# MGT.net
KiCad netlist of a schematic drawn in Altium Designer
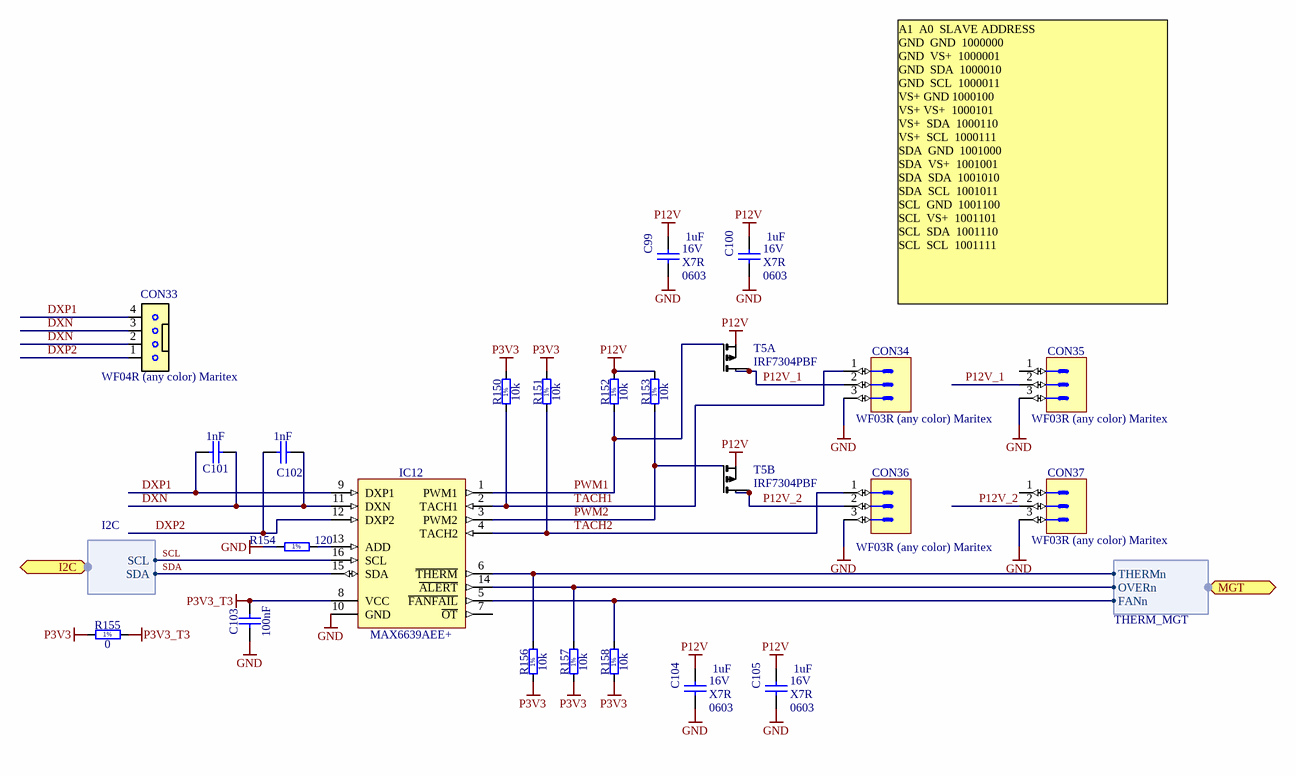
[diagram p0: MGT.SchDoc]

(export (version "E")
  (design (tool "Eeschema 10.0.6"))
  (components
    (comp (ref "C99")
      (value "1uF")
      (footprint "CAPC1608X87N")
      (description "Non-polarised capacitor")
      (fields
        (field (name "PART NUMBER") "CC0603_1UF_16V_10%_X7R")
        (field (name "VOLTAGE") "16V")
        (field (name "TC") "X7R")
        (field (name "TOLERANCE") "±10%")
        (field (name "CASE") "0603")
        (field (name "AUTHOR") "CERN DEM JLC")
      )
      (libsource (lib "Capacitors") (part "Capacitor - non polarized"))
    )
    (comp (ref "C100")
      (value "1uF")
      (footprint "CAPC1608X87N")
      (description "Non-polarised capacitor")
      (fields
        (field (name "PART NUMBER") "CC0603_1UF_16V_10%_X7R")
        (field (name "VOLTAGE") "16V")
        (field (name "TC") "X7R")
        (field (name "TOLERANCE") "±10%")
        (field (name "CASE") "0603")
        (field (name "AUTHOR") "CERN DEM JLC")
      )
      (libsource (lib "Capacitors") (part "Capacitor - non polarized"))
    )
    (comp (ref "C101")
      (value "1nF")
      (footprint "CAPC1608X87N")
      (description "Non-polarised capacitor")
      (fields
        (field (name "PART NUMBER") "CC0603_1NF_50V_10%_X7R")
        (field (name "VOLTAGE") "50V")
        (field (name "AUTHOR") "CERN DEM JLC")
      )
      (libsource (lib "Capacitors") (part "Capacitor - non polarized"))
    )
    (comp (ref "C102")
      (value "1nF")
      (footprint "CAPC1608X87N")
      (description "Non-polarised capacitor")
      (fields
        (field (name "PART NUMBER") "CC0603_1NF_50V_10%_X7R")
        (field (name "VOLTAGE") "50V")
        (field (name "AUTHOR") "CERN DEM JLC")
      )
      (libsource (lib "Capacitors") (part "Capacitor - non polarized"))
    )
    (comp (ref "C103")
      (value "100nF")
      (footprint "CAPC0603X33N")
      (description "Non-polarised capacitor")
      (fields
        (field (name "PART NUMBER") "CC0201_100NF_6.3V_10%_X5R")
        (field (name "VOLTAGE") "6.3V")
        (field (name "AUTHOR") "CERN DEM JLC")
      )
      (libsource (lib "Capacitors") (part "Capacitor - non polarized"))
    )
    (comp (ref "C104")
      (value "1uF")
      (footprint "CAPC1608X87N")
      (description "Non-polarised capacitor")
      (fields
        (field (name "PART NUMBER") "CC0603_1UF_16V_10%_X7R")
        (field (name "VOLTAGE") "16V")
        (field (name "TC") "X7R")
        (field (name "TOLERANCE") "±10%")
        (field (name "CASE") "0603")
        (field (name "AUTHOR") "CERN DEM JLC")
      )
      (libsource (lib "Capacitors") (part "Capacitor - non polarized"))
    )
    (comp (ref "C105")
      (value "1uF")
      (footprint "CAPC1608X87N")
      (description "Non-polarised capacitor")
      (fields
        (field (name "PART NUMBER") "CC0603_1UF_16V_10%_X7R")
        (field (name "VOLTAGE") "16V")
        (field (name "TC") "X7R")
        (field (name "TOLERANCE") "±10%")
        (field (name "CASE") "0603")
        (field (name "AUTHOR") "CERN DEM JLC")
      )
      (libsource (lib "Capacitors") (part "Capacitor - non polarized"))
    )
    (comp (ref "CON33")
      (value "WF04R (any color) Maritex")
      (footprint "CON_0022057048")
      (description "2.54mm crimped terminal header")
      (libsource (lib "LIBRARY_SCH") (part "CON_4_2.54_RA_key"))
    )
    (comp (ref "CON34")
      (value "WF03R (any color) Maritex")
      (footprint "MOLEX_22-05-7038")
      (description "Connector 3 Male")
      (fields
        (field (name "PART NUMBER") "MOLEX_22-05-7038")
        (field (name "MANUFACTURER") "MOLEX")
        (field (name "AUTHOR") "CERN DEM JLC")
      )
      (libsource (lib "Connectors") (part "Connector 3 Male"))
    )
    (comp (ref "CON35")
      (value "WF03R (any color) Maritex")
      (footprint "MOLEX_22-05-7038")
      (description "Connector 3 Male")
      (fields
        (field (name "PART NUMBER") "MOLEX_22-05-7038")
        (field (name "MANUFACTURER") "MOLEX")
        (field (name "AUTHOR") "CERN DEM JLC")
      )
      (libsource (lib "Connectors") (part "Connector 3 Male"))
    )
    (comp (ref "CON36")
      (value "WF03R (any color) Maritex")
      (footprint "MOLEX_22-05-7038")
      (description "Connector 3 Male")
      (fields
        (field (name "PART NUMBER") "MOLEX_22-05-7038")
        (field (name "MANUFACTURER") "MOLEX")
        (field (name "AUTHOR") "CERN DEM JLC")
      )
      (libsource (lib "Connectors") (part "Connector 3 Male"))
    )
    (comp (ref "CON37")
      (value "WF03R (any color) Maritex")
      (footprint "MOLEX_22-05-7038")
      (description "Connector 3 Male")
      (fields
        (field (name "PART NUMBER") "MOLEX_22-05-7038")
        (field (name "MANUFACTURER") "MOLEX")
        (field (name "AUTHOR") "CERN DEM JLC")
      )
      (libsource (lib "Connectors") (part "Connector 3 Male"))
    )
    (comp (ref "IC12")
      (value "MAX6639AEE+")
      (footprint "SOP63P600X175-16N")
      (description "2-Channel Temperature Monitor with Dual, Automatic, PWM Fan-Speed Controller")
      (fields (field (name "MANUFACTURER") "MAXIM") (field (name "AUTHOR") "CERN DEM JLC"))
      (libsource (lib "ICs And Semiconductors") (part "MAX6639AEE+"))
    )
    (comp (ref "R150")
      (value "10k")
      (footprint "RESC1005X40N")
      (description "Resistor - 1%")
      (fields
        (field (name "PART NUMBER") "R0402_10K_1%_0.0625W_100PPM")
        (field (name "POWER") "0.0625W")
        (field (name "AUTHOR") "CERN DEM JLC")
      )
      (libsource (lib "Resistors") (part "Resistor - 1%"))
    )
    (comp (ref "R151")
      (value "10k")
      (footprint "RESC1005X40N")
      (description "Resistor - 1%")
      (fields
        (field (name "PART NUMBER") "R0402_10K_1%_0.0625W_100PPM")
        (field (name "POWER") "0.0625W")
        (field (name "AUTHOR") "CERN DEM JLC")
      )
      (libsource (lib "Resistors") (part "Resistor - 1%"))
    )
    (comp (ref "R152")
      (value "10k")
      (footprint "RESC1005X40N")
      (description "Resistor - 1%")
      (fields
        (field (name "PART NUMBER") "R0402_10K_1%_0.0625W_100PPM")
        (field (name "POWER") "0.0625W")
        (field (name "AUTHOR") "CERN DEM JLC")
      )
      (libsource (lib "Resistors") (part "Resistor - 1%"))
    )
    (comp (ref "R153")
      (value "10k")
      (footprint "RESC1005X40N")
      (description "Resistor - 1%")
      (fields
        (field (name "PART NUMBER") "R0402_10K_1%_0.0625W_100PPM")
        (field (name "POWER") "0.0625W")
        (field (name "AUTHOR") "CERN DEM JLC")
      )
      (libsource (lib "Resistors") (part "Resistor - 1%"))
    )
    (comp (ref "R154")
      (value "120")
      (footprint "RESC1005X40N")
      (description "Resistor - 1%")
      (fields
        (field (name "PART NUMBER") "R0402_120R_1%_0.0625W_100PPM")
        (field (name "POWER") "0.0625W")
        (field (name "AUTHOR") "CERN DEM JLC")
      )
      (libsource (lib "Resistors") (part "Resistor - 1%"))
    )
    (comp (ref "R155")
      (value "0")
      (footprint "RESC1608X55N")
      (description "Resistor - 1%")
      (fields
        (field (name "PART NUMBER") "R0603_0R_JUMPER")
        (field (name "MANUFACTURER") "GENERIC")
        (field (name "AUTHOR") "CERN DEM JLC")
      )
      (libsource (lib "Resistors") (part "Resistor - 1%"))
    )
    (comp (ref "R156")
      (value "10k")
      (footprint "RESC1005X40N")
      (description "Resistor - 1%")
      (fields
        (field (name "PART NUMBER") "R0402_10K_1%_0.0625W_100PPM")
        (field (name "POWER") "0.0625W")
        (field (name "AUTHOR") "CERN DEM JLC")
      )
      (libsource (lib "Resistors") (part "Resistor - 1%"))
    )
    (comp (ref "R157")
      (value "10k")
      (footprint "RESC1005X40N")
      (description "Resistor - 1%")
      (fields
        (field (name "PART NUMBER") "R0402_10K_1%_0.0625W_100PPM")
        (field (name "POWER") "0.0625W")
        (field (name "AUTHOR") "CERN DEM JLC")
      )
      (libsource (lib "Resistors") (part "Resistor - 1%"))
    )
    (comp (ref "R158")
      (value "10k")
      (footprint "RESC1005X40N")
      (description "Resistor - 1%")
      (fields
        (field (name "PART NUMBER") "R0402_10K_1%_0.0625W_100PPM")
        (field (name "POWER") "0.0625W")
        (field (name "AUTHOR") "CERN DEM JLC")
      )
      (libsource (lib "Resistors") (part "Resistor - 1%"))
    )
    (comp (ref "T5")
      (value "IRF7304PBF")
      (footprint "so-8")
      (description "dual PMOS   20V 4,3A 2,0W 0,09R")
      (libsource (lib "LIBRARY_SCH") (part "Q_IRF7304"))
    )
  )
  (nets
    (net (code "3") (name "/DXN") (class "Default")
      (node (ref "C101") (pin "1") (pinfunction "1_1") (pintype "passive"))
      (node (ref "C102") (pin "1") (pinfunction "1_1") (pintype "passive"))
      (node (ref "CON33") (pin "2") (pinfunction "2_2") (pintype "bidirectional"))
      (node (ref "CON33") (pin "3") (pinfunction "3_3") (pintype "bidirectional"))
      (node (ref "IC12") (pin "11") (pinfunction "DXN_11") (pintype "input"))
    )
    (net (code "4") (name "/DXP1") (class "Default")
      (node (ref "C101") (pin "2") (pinfunction "2_2") (pintype "passive"))
      (node (ref "CON33") (pin "4") (pinfunction "4_4") (pintype "bidirectional"))
      (node (ref "IC12") (pin "9") (pinfunction "DXP1_9") (pintype "input"))
    )
    (net (code "5") (name "/DXP2") (class "Default")
      (node (ref "C102") (pin "2") (pinfunction "2_2") (pintype "passive"))
      (node (ref "CON33") (pin "1") (pinfunction "1_1") (pintype "bidirectional"))
      (node (ref "IC12") (pin "12") (pinfunction "DXP2_12") (pintype "input"))
    )
    (net (code "6") (name "/P12V_1") (class "Default")
      (node (ref "CON34") (pin "2") (pinfunction "2_2") (pintype "bidirectional"))
      (node (ref "CON35") (pin "2") (pinfunction "2_2") (pintype "bidirectional"))
      (node (ref "T5") (pin "7") (pinfunction "D1_7") (pintype "passive"))
      (node (ref "T5") (pin "8") (pinfunction "D1_8") (pintype "passive"))
    )
    (net (code "7") (name "/P12V_2") (class "Default")
      (node (ref "CON36") (pin "2") (pinfunction "2_2") (pintype "bidirectional"))
      (node (ref "CON37") (pin "2") (pinfunction "2_2") (pintype "bidirectional"))
      (node (ref "T5") (pin "5") (pinfunction "D2_5") (pintype "passive"))
      (node (ref "T5") (pin "6") (pinfunction "D2_6") (pintype "passive"))
    )
    (net (code "8") (name "/PWM1") (class "Default")
      (node (ref "IC12") (pin "1") (pinfunction "PWM1_1") (pintype "output"))
      (node (ref "R152") (pin "1") (pinfunction "1_1") (pintype "passive"))
      (node (ref "T5") (pin "2") (pinfunction "G1_2") (pintype "input"))
    )
    (net (code "9") (name "/PWM2") (class "Default")
      (node (ref "IC12") (pin "3") (pinfunction "PWM2_3") (pintype "output"))
      (node (ref "R153") (pin "1") (pinfunction "1_1") (pintype "passive"))
      (node (ref "T5") (pin "4") (pinfunction "G2_4") (pintype "input"))
    )
    (net (code "10") (name "/SCL") (class "Default")
      (node (ref "IC12") (pin "16") (pinfunction "SCL_16") (pintype "input"))
    )
    (net (code "11") (name "/SDA") (class "Default")
      (node (ref "IC12") (pin "15") (pinfunction "SDA_15") (pintype "bidirectional"))
    )
    (net (code "12") (name "/TACH1") (class "Default")
      (node (ref "CON34") (pin "1") (pinfunction "1_1") (pintype "bidirectional"))
      (node (ref "IC12") (pin "2") (pinfunction "TACH1_2") (pintype "input"))
      (node (ref "R150") (pin "1") (pinfunction "1_1") (pintype "passive"))
    )
    (net (code "13") (name "/TACH2") (class "Default")
      (node (ref "CON36") (pin "1") (pinfunction "1_1") (pintype "bidirectional"))
      (node (ref "IC12") (pin "4") (pinfunction "TACH2_4") (pintype "input"))
      (node (ref "R151") (pin "1") (pinfunction "1_1") (pintype "passive"))
    )
    (net (code "16") (name "GND") (class "Default")
      (node (ref "C100") (pin "1") (pinfunction "1_1") (pintype "passive"))
      (node (ref "C103") (pin "1") (pinfunction "1_1") (pintype "passive"))
      (node (ref "C104") (pin "1") (pinfunction "1_1") (pintype "passive"))
      (node (ref "C105") (pin "1") (pinfunction "1_1") (pintype "passive"))
      (node (ref "C99") (pin "1") (pinfunction "1_1") (pintype "passive"))
      (node (ref "CON34") (pin "3") (pinfunction "3_3") (pintype "bidirectional"))
      (node (ref "CON35") (pin "3") (pinfunction "3_3") (pintype "bidirectional"))
      (node (ref "CON36") (pin "3") (pinfunction "3_3") (pintype "bidirectional"))
      (node (ref "CON37") (pin "3") (pinfunction "3_3") (pintype "bidirectional"))
      (node (ref "IC12") (pin "10") (pinfunction "GND_10") (pintype "power_in"))
      (node (ref "R154") (pin "1") (pinfunction "1_1") (pintype "passive"))
    )
    (net (code "17") (name "Net-(IC12-ADD)") (class "Default")
      (node (ref "IC12") (pin "13") (pinfunction "ADD_13") (pintype "input"))
      (node (ref "R154") (pin "2") (pinfunction "2_2") (pintype "passive"))
    )
    (net (code "18") (name "Net-(IC12-~{ALERT})") (class "Default")
      (node (ref "IC12") (pin "14") (pinfunction "~{ALERT}_14") (pintype "output"))
      (node (ref "R157") (pin "2") (pinfunction "2_2") (pintype "passive"))
    )
    (net (code "19") (name "Net-(IC12-~{FANFAIL})") (class "Default")
      (node (ref "IC12") (pin "5") (pinfunction "~{FANFAIL}_5") (pintype "output"))
      (node (ref "R158") (pin "2") (pinfunction "2_2") (pintype "passive"))
    )
    (net (code "20") (name "Net-(IC12-~{THERM})") (class "Default")
      (node (ref "IC12") (pin "6") (pinfunction "~{THERM}_6") (pintype "output"))
      (node (ref "R156") (pin "2") (pinfunction "2_2") (pintype "passive"))
    )
    (net (code "21") (name "P3V3") (class "Default")
      (node (ref "R150") (pin "2") (pinfunction "2_2") (pintype "passive"))
      (node (ref "R151") (pin "2") (pinfunction "2_2") (pintype "passive"))
      (node (ref "R155") (pin "1") (pinfunction "1_1") (pintype "passive"))
      (node (ref "R156") (pin "1") (pinfunction "1_1") (pintype "passive"))
      (node (ref "R157") (pin "1") (pinfunction "1_1") (pintype "passive"))
      (node (ref "R158") (pin "1") (pinfunction "1_1") (pintype "passive"))
    )
    (net (code "22") (name "P3V3_T3") (class "Default")
      (node (ref "C103") (pin "2") (pinfunction "2_2") (pintype "passive"))
      (node (ref "IC12") (pin "8") (pinfunction "VCC_8") (pintype "power_in"))
      (node (ref "R155") (pin "2") (pinfunction "2_2") (pintype "passive"))
    )
    (net (code "23") (name "P12V") (class "Default")
      (node (ref "C100") (pin "2") (pinfunction "2_2") (pintype "passive"))
      (node (ref "C104") (pin "2") (pinfunction "2_2") (pintype "passive"))
      (node (ref "C105") (pin "2") (pinfunction "2_2") (pintype "passive"))
      (node (ref "C99") (pin "2") (pinfunction "2_2") (pintype "passive"))
      (node (ref "R152") (pin "2") (pinfunction "2_2") (pintype "passive"))
      (node (ref "R153") (pin "2") (pinfunction "2_2") (pintype "passive"))
      (node (ref "T5") (pin "1") (pinfunction "S1_1") (pintype "passive"))
      (node (ref "T5") (pin "3") (pinfunction "S2_3") (pintype "passive"))
    )
    (net (code "24") (name "unconnected-(CON35-Pad1)") (class "Default")
      (node (ref "CON35") (pin "1") (pinfunction "1_1") (pintype "bidirectional"))
    )
    (net (code "25") (name "unconnected-(CON37-Pad1)") (class "Default")
      (node (ref "CON37") (pin "1") (pinfunction "1_1") (pintype "bidirectional"))
    )
    (net (code "26") (name "unconnected-(IC12-~{OT}-Pad7)") (class "Default")
      (node (ref "IC12") (pin "7") (pinfunction "~{OT}_7") (pintype "output"))
    )
  )
)
